# SMA_Single_Filter.net
KiCad netlist of a schematic drawn in Altium Designer
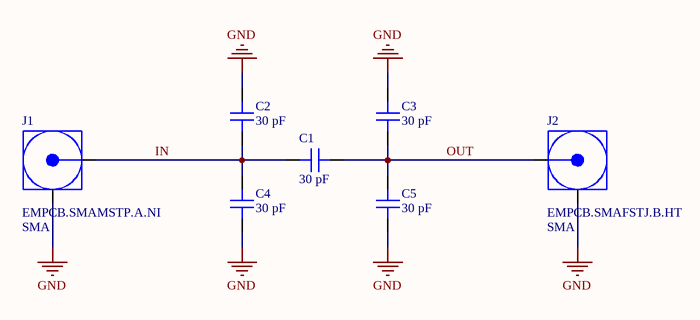
[diagram p0: SMA Single Filter.SchDoc]

(export (version "E")
  (design (tool "Eeschema 10.0.6"))
  (components
    (comp (ref "C1")
      (value "30 pF")
      (footprint "CAP 0402_1005")
      (description "HIGH-Q MLC CAPACITOR, C-SERIES,")
      (fields
        (field (name "PART NUMBER") "QCCF251Q300J1GV001T")
        (field (name "MANUFACTURER") "Johanson Technology Inc.")
      )
      (libsource (lib "altiumlibrary.com") (part "Capacitor"))
    )
    (comp (ref "C2")
      (value "30 pF")
      (footprint "CAP 0402_1005")
      (description "HIGH-Q MLC CAPACITOR, C-SERIES,")
      (fields
        (field (name "PART NUMBER") "QCCF251Q300J1GV001T")
        (field (name "MANUFACTURER") "Johanson Technology Inc.")
      )
      (libsource (lib "altiumlibrary.com") (part "Capacitor"))
    )
    (comp (ref "C3")
      (value "30 pF")
      (footprint "CAP 0402_1005")
      (description "HIGH-Q MLC CAPACITOR, C-SERIES,")
      (fields
        (field (name "PART NUMBER") "QCCF251Q300J1GV001T")
        (field (name "MANUFACTURER") "Johanson Technology Inc.")
      )
      (libsource (lib "altiumlibrary.com") (part "Capacitor"))
    )
    (comp (ref "C4")
      (value "30 pF")
      (footprint "CAP 0402_1005")
      (description "HIGH-Q MLC CAPACITOR, C-SERIES,")
      (fields
        (field (name "PART NUMBER") "QCCF251Q300J1GV001T")
        (field (name "MANUFACTURER") "Johanson Technology Inc.")
      )
      (libsource (lib "altiumlibrary.com") (part "Capacitor"))
    )
    (comp (ref "C5")
      (value "30 pF")
      (footprint "CAP 0402_1005")
      (description "HIGH-Q MLC CAPACITOR, C-SERIES,")
      (fields
        (field (name "PART NUMBER") "QCCF251Q300J1GV001T")
        (field (name "MANUFACTURER") "Johanson Technology Inc.")
      )
      (libsource (lib "altiumlibrary.com") (part "Capacitor"))
    )
    (comp (ref "J1")
      (value "EMPCB.SMAMSTP.A.NI")
      (footprint "TAOGLAS EMPCB.SMAMSTP.A.NI")
      (description "SMA(M)ST FOR PCB EDGE MOUNT NI P")
      (fields (field (name "CONNECTOR STYLE") "SMA") (field (name "MANUFACTURER") "Taoglas Limited"))
      (libsource (lib "altiumlibrary.com") (part "COAX CONNECTOR"))
    )
    (comp (ref "J2")
      (value "EMPCB.SMAFSTJ.B.HT")
      (footprint "TAOGLAS EMPCB.SMAFSTJ.B.HT")
      (description "CONN SMA JACK STR 50OHM EDGE MNT")
      (fields (field (name "CONNECTOR STYLE") "SMA") (field (name "MANUFACTURER") "Taoglas Limited"))
      (libsource (lib "altiumlibrary.com") (part "COAX CONNECTOR"))
    )
  )
  (nets
    (net (code "1") (name "/IN") (class "Default")
      (node (ref "C1") (pin "1") (pinfunction "1_1") (pintype "passive"))
      (node (ref "C2") (pin "1") (pinfunction "1_1") (pintype "passive"))
      (node (ref "C4") (pin "2") (pinfunction "2_2") (pintype "passive"))
      (node (ref "J1") (pin "S") (pinfunction "Signal_S") (pintype "passive"))
    )
    (net (code "2") (name "/OUT") (class "Default")
      (node (ref "C1") (pin "2") (pinfunction "2_2") (pintype "passive"))
      (node (ref "C3") (pin "1") (pinfunction "1_1") (pintype "passive"))
      (node (ref "C5") (pin "2") (pinfunction "2_2") (pintype "passive"))
      (node (ref "J2") (pin "S") (pinfunction "Signal_S") (pintype "passive"))
    )
    (net (code "3") (name "GND") (class "Default")
      (node (ref "C2") (pin "2") (pinfunction "2_2") (pintype "passive"))
      (node (ref "C3") (pin "2") (pinfunction "2_2") (pintype "passive"))
      (node (ref "C4") (pin "1") (pinfunction "1_1") (pintype "passive"))
      (node (ref "C5") (pin "1") (pinfunction "1_1") (pintype "passive"))
      (node (ref "J1") (pin "G") (pinfunction "GND_G") (pintype "passive"))
      (node (ref "J2") (pin "G") (pinfunction "GND_G") (pintype "passive"))
    )
  )
)
